# GERMO.net
KiCad netlist of a schematic drawn in EAGLE
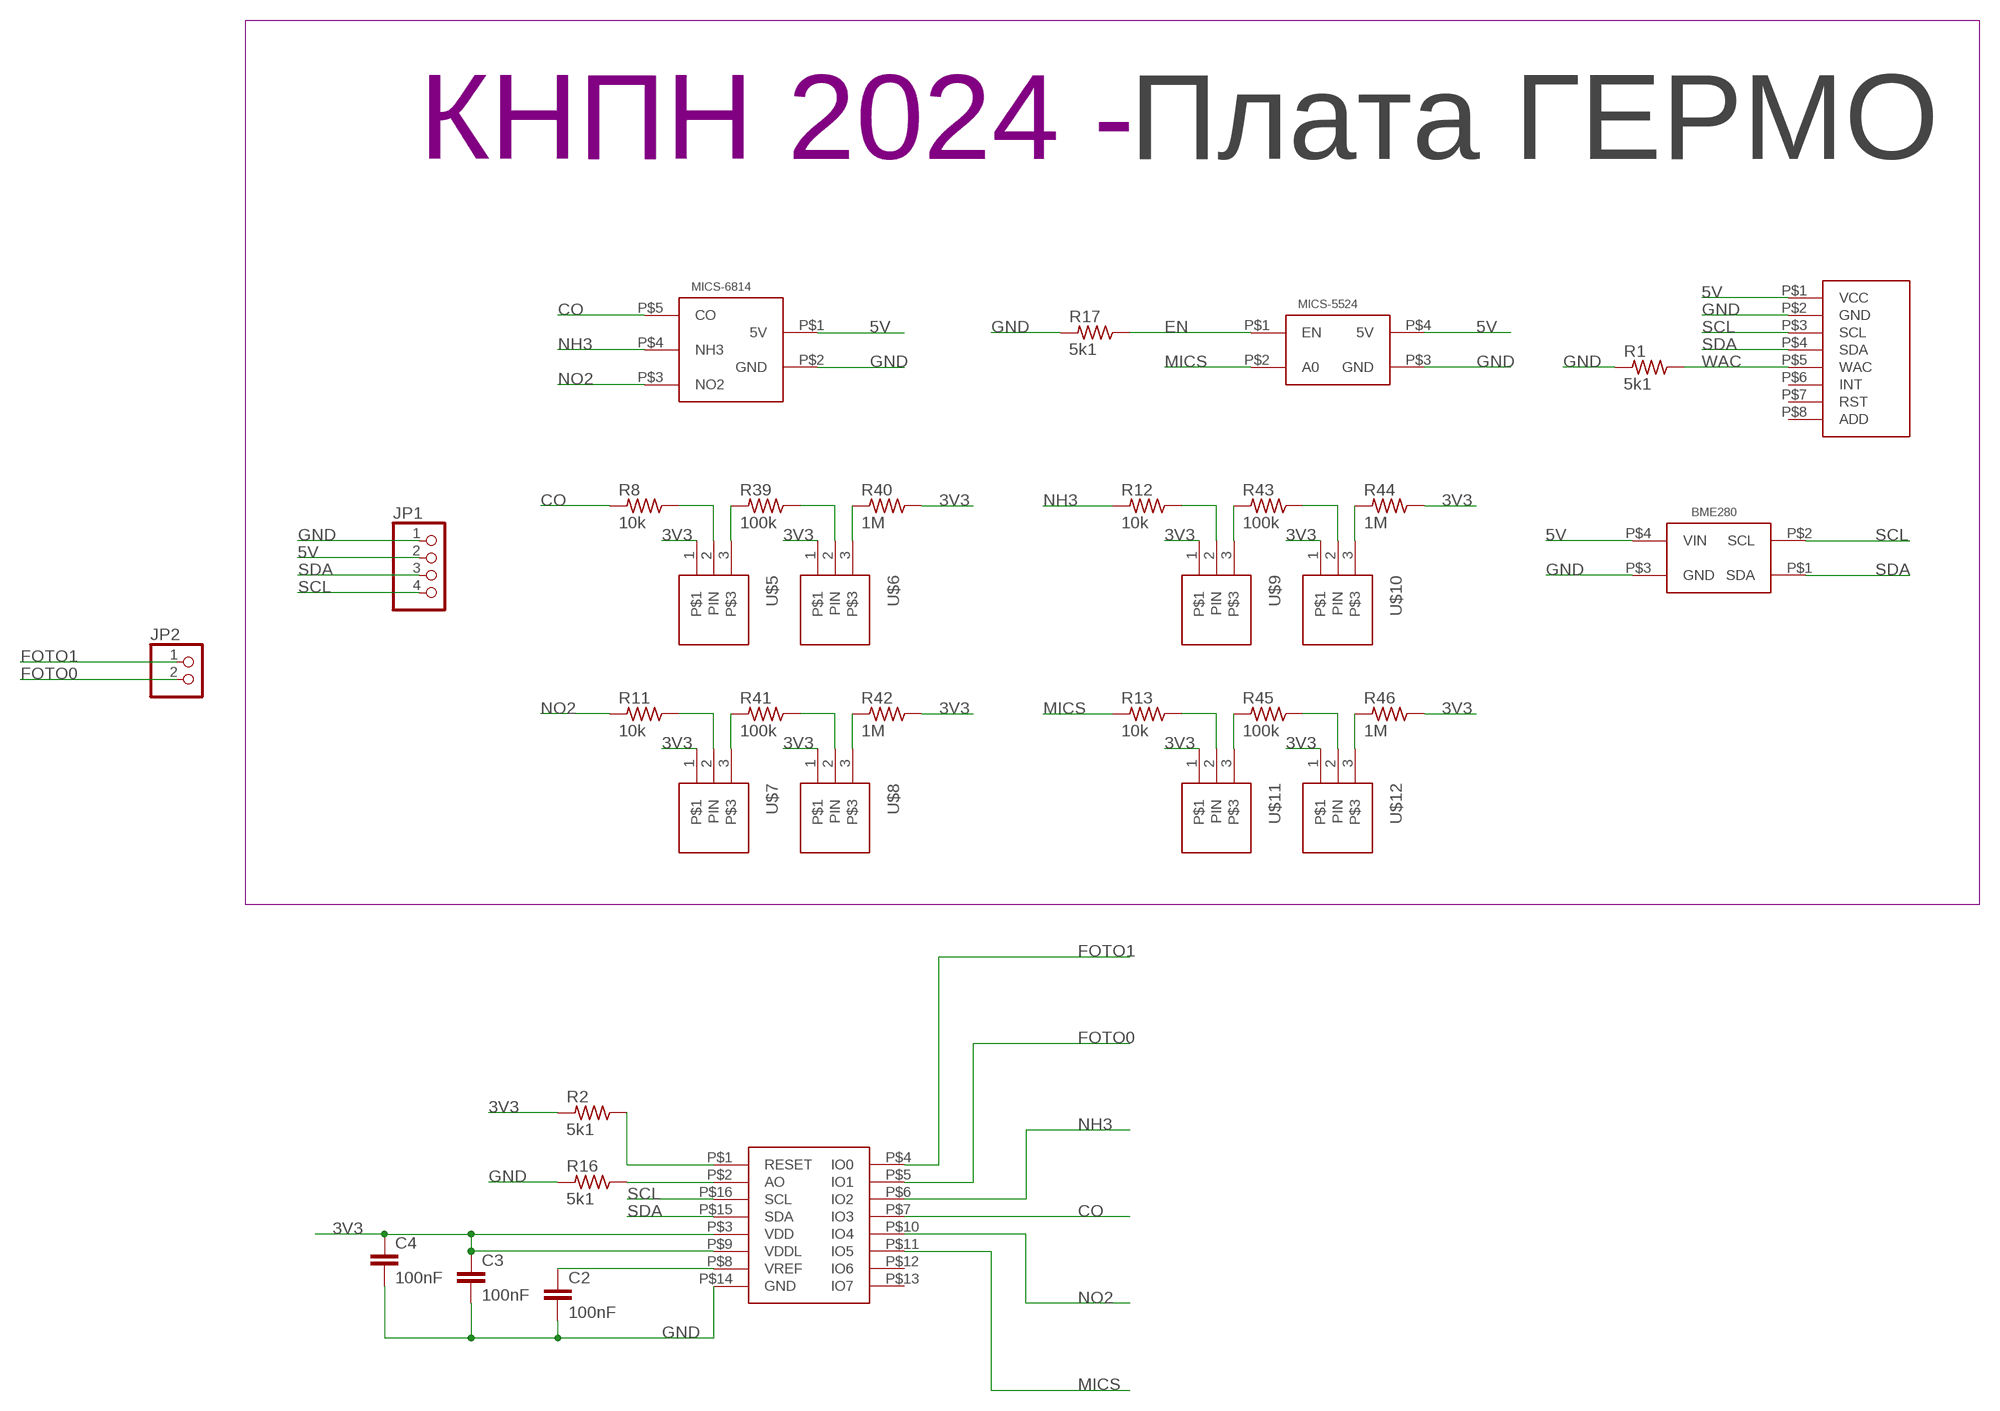
[diagram p0: schematic, sheet 1]

(export (version "E")
  (design (tool "Eeschema 10.0.6"))
  (components
    (comp (ref "BME280")
      (value "BME280BME280-PINS-ONLY")
      (footprint "eagle-import:BME280-PINS-ONLY")
      (libsource (lib "eagle-import") (part "BME280BME280-PINS-ONLY"))
    )
    (comp (ref "C2")
      (value "100nF")
      (footprint "eagle-import:C0603")
      (libsource (lib "eagle-import") (part "C-EUC0603"))
    )
    (comp (ref "C3")
      (value "100nF")
      (footprint "eagle-import:C0603")
      (libsource (lib "eagle-import") (part "C-EUC0603"))
    )
    (comp (ref "C4")
      (value "100nF")
      (footprint "eagle-import:C0603")
      (libsource (lib "eagle-import") (part "C-EUC0603"))
    )
    (comp (ref "JP1")
      (value "PINHD-1X4")
      (footprint "eagle-import:1X04")
      (libsource (lib "eagle-import") (part "PINHD-1X4"))
    )
    (comp (ref "JP2")
      (value "PINHD-1X2")
      (footprint "eagle-import:1X02")
      (libsource (lib "eagle-import") (part "PINHD-1X2"))
    )
    (comp (ref "MICS-5524")
      (value "MICS_5524")
      (footprint "eagle-import:MICS-5524")
      (libsource (lib "eagle-import") (part "MICS_5524"))
    )
    (comp (ref "MICS-6814")
      (value "MICS-6814")
      (footprint "eagle-import:MICS-6814")
      (libsource (lib "eagle-import") (part "MICS-6814"))
    )
    (comp (ref "R1")
      (value "5k1")
      (footprint "eagle-import:R0603")
      (libsource (lib "eagle-import") (part "R-US_R0603"))
    )
    (comp (ref "R2")
      (value "5k1")
      (footprint "eagle-import:R0603")
      (libsource (lib "eagle-import") (part "R-US_R0603"))
    )
    (comp (ref "R8")
      (value "10k")
      (footprint "eagle-import:R0603")
      (libsource (lib "eagle-import") (part "R-US_R0603"))
    )
    (comp (ref "R11")
      (value "10k")
      (footprint "eagle-import:R0603")
      (libsource (lib "eagle-import") (part "R-US_R0603"))
    )
    (comp (ref "R12")
      (value "10k")
      (footprint "eagle-import:R0603")
      (libsource (lib "eagle-import") (part "R-US_R0603"))
    )
    (comp (ref "R13")
      (value "10k")
      (footprint "eagle-import:R0603")
      (libsource (lib "eagle-import") (part "R-US_R0603"))
    )
    (comp (ref "R16")
      (value "5k1")
      (footprint "eagle-import:R0603")
      (libsource (lib "eagle-import") (part "R-US_R0603"))
    )
    (comp (ref "R17")
      (value "5k1")
      (footprint "eagle-import:R0603")
      (libsource (lib "eagle-import") (part "R-US_R0603"))
    )
    (comp (ref "R39")
      (value "100k")
      (footprint "eagle-import:R0603")
      (libsource (lib "eagle-import") (part "R-US_R0603"))
    )
    (comp (ref "R40")
      (value "1M")
      (footprint "eagle-import:R0603")
      (libsource (lib "eagle-import") (part "R-US_R0603"))
    )
    (comp (ref "R41")
      (value "100k")
      (footprint "eagle-import:R0603")
      (libsource (lib "eagle-import") (part "R-US_R0603"))
    )
    (comp (ref "R42")
      (value "1M")
      (footprint "eagle-import:R0603")
      (libsource (lib "eagle-import") (part "R-US_R0603"))
    )
    (comp (ref "R43")
      (value "100k")
      (footprint "eagle-import:R0603")
      (libsource (lib "eagle-import") (part "R-US_R0603"))
    )
    (comp (ref "R44")
      (value "1M")
      (footprint "eagle-import:R0603")
      (libsource (lib "eagle-import") (part "R-US_R0603"))
    )
    (comp (ref "R45")
      (value "100k")
      (footprint "eagle-import:R0603")
      (libsource (lib "eagle-import") (part "R-US_R0603"))
    )
    (comp (ref "R46")
      (value "1M")
      (footprint "eagle-import:R0603")
      (libsource (lib "eagle-import") (part "R-US_R0603"))
    )
    (comp (ref "U$2")
      (value "Плата ГЕРМО")
      (footprint "eagle-import:LOGO")
      (libsource (lib "eagle-import") (part "LOGOPCB-{dblquote}{dblquote}"))
    )
    (comp (ref "U$4")
      (value "CCS811")
      (footprint "eagle-import:CSS811")
      (libsource (lib "eagle-import") (part "CCS811"))
    )
    (comp (ref "U$5")
      (value "CONNECT_3")
      (footprint "eagle-import:CONNECT_3")
      (libsource (lib "eagle-import") (part "CONNECT_3"))
    )
    (comp (ref "U$6")
      (value "CONNECT_3")
      (footprint "eagle-import:CONNECT_3")
      (libsource (lib "eagle-import") (part "CONNECT_3"))
    )
    (comp (ref "U$7")
      (value "CONNECT_3")
      (footprint "eagle-import:CONNECT_3")
      (libsource (lib "eagle-import") (part "CONNECT_3"))
    )
    (comp (ref "U$8")
      (value "CONNECT_3")
      (footprint "eagle-import:CONNECT_3")
      (libsource (lib "eagle-import") (part "CONNECT_3"))
    )
    (comp (ref "U$9")
      (value "CONNECT_3")
      (footprint "eagle-import:CONNECT_3")
      (libsource (lib "eagle-import") (part "CONNECT_3"))
    )
    (comp (ref "U$10")
      (value "CONNECT_3")
      (footprint "eagle-import:CONNECT_3")
      (libsource (lib "eagle-import") (part "CONNECT_3"))
    )
    (comp (ref "U$11")
      (value "CONNECT_3")
      (footprint "eagle-import:CONNECT_3")
      (libsource (lib "eagle-import") (part "CONNECT_3"))
    )
    (comp (ref "U$12")
      (value "CONNECT_3")
      (footprint "eagle-import:CONNECT_3")
      (libsource (lib "eagle-import") (part "CONNECT_3"))
    )
    (comp (ref "U$14")
      (value "AD5593")
      (footprint "eagle-import:AD5593")
      (libsource (lib "eagle-import") (part "AD5593"))
    )
  )
  (nets
    (net (code "1") (name "/3V3") (class "Default")
      (node (ref "C3") (pin "1") (pinfunction "1_1") (pintype "passive"))
      (node (ref "C4") (pin "1") (pinfunction "1_1") (pintype "passive"))
      (node (ref "R2") (pin "2") (pinfunction "2_2") (pintype "passive"))
      (node (ref "R40") (pin "1") (pinfunction "1_1") (pintype "passive"))
      (node (ref "R42") (pin "1") (pinfunction "1_1") (pintype "passive"))
      (node (ref "R44") (pin "1") (pinfunction "1_1") (pintype "passive"))
      (node (ref "R46") (pin "1") (pinfunction "1_1") (pintype "passive"))
      (node (ref "U$10") (pin "1") (pinfunction "P$1_1") (pintype "bidirectional"))
      (node (ref "U$11") (pin "1") (pinfunction "P$1_1") (pintype "bidirectional"))
      (node (ref "U$12") (pin "1") (pinfunction "P$1_1") (pintype "bidirectional"))
      (node (ref "U$14") (pin "P$3") (pinfunction "VDD_P$3") (pintype "bidirectional"))
      (node (ref "U$14") (pin "P$9") (pinfunction "VDDL_P$9") (pintype "bidirectional"))
      (node (ref "U$5") (pin "1") (pinfunction "P$1_1") (pintype "bidirectional"))
      (node (ref "U$6") (pin "1") (pinfunction "P$1_1") (pintype "bidirectional"))
      (node (ref "U$7") (pin "1") (pinfunction "P$1_1") (pintype "bidirectional"))
      (node (ref "U$8") (pin "1") (pinfunction "P$1_1") (pintype "bidirectional"))
      (node (ref "U$9") (pin "1") (pinfunction "P$1_1") (pintype "bidirectional"))
    )
    (net (code "2") (name "/5V") (class "Default")
      (node (ref "BME280") (pin "P$4") (pinfunction "VIN_P$4") (pintype "bidirectional"))
      (node (ref "JP1") (pin "2") (pinfunction "2_2") (pintype "passive"))
      (node (ref "MICS-5524") (pin "P$4") (pinfunction "5V_P$4") (pintype "bidirectional"))
      (node (ref "MICS-6814") (pin "P$1") (pinfunction "5V_P$1") (pintype "bidirectional"))
      (node (ref "U$4") (pin "P$1") (pinfunction "VCC_P$1") (pintype "bidirectional"))
    )
    (net (code "3") (name "/CO") (class "Default")
      (node (ref "MICS-6814") (pin "P$5") (pinfunction "CO_P$5") (pintype "bidirectional"))
      (node (ref "R8") (pin "2") (pinfunction "2_2") (pintype "passive"))
      (node (ref "U$14") (pin "P$7") (pinfunction "IO3_P$7") (pintype "bidirectional"))
    )
    (net (code "4") (name "/EN") (class "Default")
      (node (ref "MICS-5524") (pin "P$1") (pinfunction "EN_P$1") (pintype "bidirectional"))
      (node (ref "R17") (pin "1") (pinfunction "1_1") (pintype "passive"))
    )
    (net (code "5") (name "/FOTO0") (class "Default")
      (node (ref "JP2") (pin "2") (pinfunction "2_2") (pintype "passive"))
      (node (ref "U$14") (pin "P$5") (pinfunction "IO1_P$5") (pintype "bidirectional"))
    )
    (net (code "6") (name "/FOTO1") (class "Default")
      (node (ref "JP2") (pin "1") (pinfunction "1_1") (pintype "passive"))
      (node (ref "U$14") (pin "P$4") (pinfunction "IO0_P$4") (pintype "bidirectional"))
    )
    (net (code "7") (name "/GND") (class "Default")
      (node (ref "BME280") (pin "P$3") (pinfunction "GND_P$3") (pintype "bidirectional"))
      (node (ref "C2") (pin "2") (pinfunction "2_2") (pintype "passive"))
      (node (ref "C3") (pin "2") (pinfunction "2_2") (pintype "passive"))
      (node (ref "C4") (pin "2") (pinfunction "2_2") (pintype "passive"))
      (node (ref "JP1") (pin "1") (pinfunction "1_1") (pintype "passive"))
      (node (ref "MICS-5524") (pin "P$3") (pinfunction "GND_P$3") (pintype "bidirectional"))
      (node (ref "MICS-6814") (pin "P$2") (pinfunction "GND_P$2") (pintype "bidirectional"))
      (node (ref "R1") (pin "2") (pinfunction "2_2") (pintype "passive"))
      (node (ref "R16") (pin "2") (pinfunction "2_2") (pintype "passive"))
      (node (ref "R17") (pin "2") (pinfunction "2_2") (pintype "passive"))
      (node (ref "U$14") (pin "P$14") (pinfunction "GND_P$14") (pintype "bidirectional"))
      (node (ref "U$4") (pin "P$2") (pinfunction "GND_P$2") (pintype "bidirectional"))
    )
    (net (code "8") (name "/MICS") (class "Default")
      (node (ref "MICS-5524") (pin "P$2") (pinfunction "A0_P$2") (pintype "bidirectional"))
      (node (ref "R13") (pin "2") (pinfunction "2_2") (pintype "passive"))
      (node (ref "U$14") (pin "P$11") (pinfunction "IO5_P$11") (pintype "bidirectional"))
    )
    (net (code "9") (name "/NH3") (class "Default")
      (node (ref "MICS-6814") (pin "P$4") (pinfunction "NH3_P$4") (pintype "bidirectional"))
      (node (ref "R12") (pin "2") (pinfunction "2_2") (pintype "passive"))
      (node (ref "U$14") (pin "P$6") (pinfunction "IO2_P$6") (pintype "bidirectional"))
    )
    (net (code "10") (name "/NO2") (class "Default")
      (node (ref "MICS-6814") (pin "P$3") (pinfunction "NO2_P$3") (pintype "bidirectional"))
      (node (ref "R11") (pin "2") (pinfunction "2_2") (pintype "passive"))
      (node (ref "U$14") (pin "P$10") (pinfunction "IO4_P$10") (pintype "bidirectional"))
    )
    (net (code "11") (name "/SCL") (class "Default")
      (node (ref "BME280") (pin "P$2") (pinfunction "SCL_P$2") (pintype "bidirectional"))
      (node (ref "JP1") (pin "4") (pinfunction "4_4") (pintype "passive"))
      (node (ref "U$14") (pin "P$16") (pinfunction "SCL_P$16") (pintype "bidirectional"))
      (node (ref "U$4") (pin "P$3") (pinfunction "SCL_P$3") (pintype "bidirectional"))
    )
    (net (code "12") (name "/SDA") (class "Default")
      (node (ref "BME280") (pin "P$1") (pinfunction "SDA_P$1") (pintype "bidirectional"))
      (node (ref "JP1") (pin "3") (pinfunction "3_3") (pintype "passive"))
      (node (ref "U$14") (pin "P$15") (pinfunction "SDA_P$15") (pintype "bidirectional"))
      (node (ref "U$4") (pin "P$4") (pinfunction "SDA_P$4") (pintype "bidirectional"))
    )
    (net (code "13") (name "/WAC") (class "Default")
      (node (ref "R1") (pin "1") (pinfunction "1_1") (pintype "passive"))
      (node (ref "U$4") (pin "P$5") (pinfunction "WAC_P$5") (pintype "bidirectional"))
    )
    (net (code "14") (name "Net-(U$5-P$3)") (class "Default")
      (node (ref "R39") (pin "2") (pinfunction "2_2") (pintype "passive"))
      (node (ref "U$5") (pin "3") (pinfunction "P$3_3") (pintype "bidirectional"))
    )
    (net (code "15") (name "Net-(U$5-PIN)") (class "Default")
      (node (ref "R8") (pin "1") (pinfunction "1_1") (pintype "passive"))
      (node (ref "U$5") (pin "2") (pinfunction "PIN_2") (pintype "bidirectional"))
    )
    (net (code "16") (name "Net-(U$6-P$3)") (class "Default")
      (node (ref "R40") (pin "2") (pinfunction "2_2") (pintype "passive"))
      (node (ref "U$6") (pin "3") (pinfunction "P$3_3") (pintype "bidirectional"))
    )
    (net (code "17") (name "Net-(U$6-PIN)") (class "Default")
      (node (ref "R39") (pin "1") (pinfunction "1_1") (pintype "passive"))
      (node (ref "U$6") (pin "2") (pinfunction "PIN_2") (pintype "bidirectional"))
    )
    (net (code "18") (name "Net-(U$7-P$3)") (class "Default")
      (node (ref "R41") (pin "2") (pinfunction "2_2") (pintype "passive"))
      (node (ref "U$7") (pin "3") (pinfunction "P$3_3") (pintype "bidirectional"))
    )
    (net (code "19") (name "Net-(U$7-PIN)") (class "Default")
      (node (ref "R11") (pin "1") (pinfunction "1_1") (pintype "passive"))
      (node (ref "U$7") (pin "2") (pinfunction "PIN_2") (pintype "bidirectional"))
    )
    (net (code "20") (name "Net-(U$8-P$3)") (class "Default")
      (node (ref "R42") (pin "2") (pinfunction "2_2") (pintype "passive"))
      (node (ref "U$8") (pin "3") (pinfunction "P$3_3") (pintype "bidirectional"))
    )
    (net (code "21") (name "Net-(U$8-PIN)") (class "Default")
      (node (ref "R41") (pin "1") (pinfunction "1_1") (pintype "passive"))
      (node (ref "U$8") (pin "2") (pinfunction "PIN_2") (pintype "bidirectional"))
    )
    (net (code "22") (name "Net-(U$9-P$3)") (class "Default")
      (node (ref "R43") (pin "2") (pinfunction "2_2") (pintype "passive"))
      (node (ref "U$9") (pin "3") (pinfunction "P$3_3") (pintype "bidirectional"))
    )
    (net (code "23") (name "Net-(U$9-PIN)") (class "Default")
      (node (ref "R12") (pin "1") (pinfunction "1_1") (pintype "passive"))
      (node (ref "U$9") (pin "2") (pinfunction "PIN_2") (pintype "bidirectional"))
    )
    (net (code "24") (name "Net-(U$10-P$3)") (class "Default")
      (node (ref "R44") (pin "2") (pinfunction "2_2") (pintype "passive"))
      (node (ref "U$10") (pin "3") (pinfunction "P$3_3") (pintype "bidirectional"))
    )
    (net (code "25") (name "Net-(U$10-PIN)") (class "Default")
      (node (ref "R43") (pin "1") (pinfunction "1_1") (pintype "passive"))
      (node (ref "U$10") (pin "2") (pinfunction "PIN_2") (pintype "bidirectional"))
    )
    (net (code "26") (name "Net-(U$11-P$3)") (class "Default")
      (node (ref "R45") (pin "2") (pinfunction "2_2") (pintype "passive"))
      (node (ref "U$11") (pin "3") (pinfunction "P$3_3") (pintype "bidirectional"))
    )
    (net (code "27") (name "Net-(U$11-PIN)") (class "Default")
      (node (ref "R13") (pin "1") (pinfunction "1_1") (pintype "passive"))
      (node (ref "U$11") (pin "2") (pinfunction "PIN_2") (pintype "bidirectional"))
    )
    (net (code "28") (name "Net-(U$12-P$3)") (class "Default")
      (node (ref "R46") (pin "2") (pinfunction "2_2") (pintype "passive"))
      (node (ref "U$12") (pin "3") (pinfunction "P$3_3") (pintype "bidirectional"))
    )
    (net (code "29") (name "Net-(U$12-PIN)") (class "Default")
      (node (ref "R45") (pin "1") (pinfunction "1_1") (pintype "passive"))
      (node (ref "U$12") (pin "2") (pinfunction "PIN_2") (pintype "bidirectional"))
    )
    (net (code "30") (name "Net-(U$14-AO)") (class "Default")
      (node (ref "R16") (pin "1") (pinfunction "1_1") (pintype "passive"))
      (node (ref "U$14") (pin "P$2") (pinfunction "AO_P$2") (pintype "bidirectional"))
    )
    (net (code "31") (name "Net-(U$14-RESET)") (class "Default")
      (node (ref "R2") (pin "1") (pinfunction "1_1") (pintype "passive"))
      (node (ref "U$14") (pin "P$1") (pinfunction "RESET_P$1") (pintype "bidirectional"))
    )
    (net (code "32") (name "Net-(U$14-VREF)") (class "Default")
      (node (ref "C2") (pin "1") (pinfunction "1_1") (pintype "passive"))
      (node (ref "U$14") (pin "P$8") (pinfunction "VREF_P$8") (pintype "bidirectional"))
    )
    (net (code "33") (name "unconnected-(U$4-ADD-PadP$8)") (class "Default")
      (node (ref "U$4") (pin "P$8") (pinfunction "ADD_P$8") (pintype "bidirectional"))
    )
    (net (code "34") (name "unconnected-(U$4-INT-PadP$6)") (class "Default")
      (node (ref "U$4") (pin "P$6") (pinfunction "INT_P$6") (pintype "bidirectional"))
    )
    (net (code "35") (name "unconnected-(U$4-RST-PadP$7)") (class "Default")
      (node (ref "U$4") (pin "P$7") (pinfunction "RST_P$7") (pintype "bidirectional"))
    )
    (net (code "36") (name "unconnected-(U$14-IO6-PadP$12)") (class "Default")
      (node (ref "U$14") (pin "P$12") (pinfunction "IO6_P$12") (pintype "bidirectional"))
    )
    (net (code "37") (name "unconnected-(U$14-IO7-PadP$13)") (class "Default")
      (node (ref "U$14") (pin "P$13") (pinfunction "IO7_P$13") (pintype "bidirectional"))
    )
  )
)
